# DAC_OutputStage_4.net
KiCad netlist of a schematic drawn in EAGLE
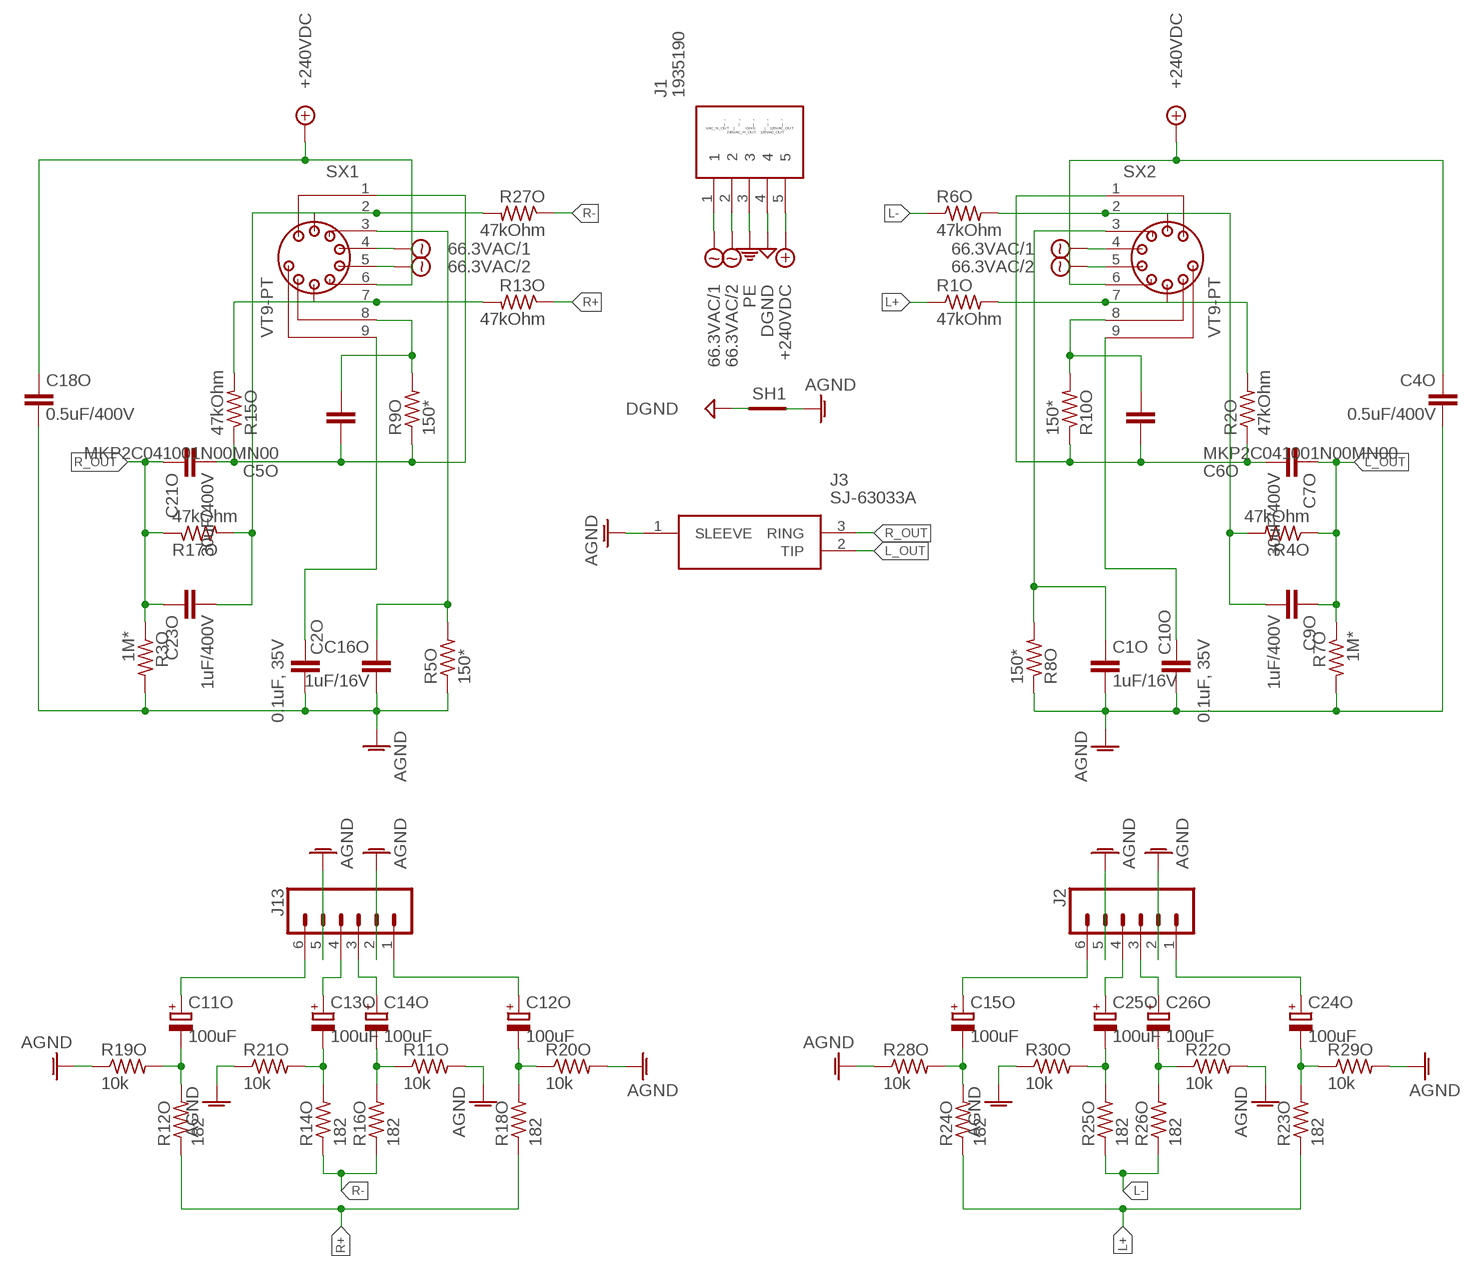
[diagram p0: schematic, sheet 1]

(export (version "E")
  (design (tool "Eeschema 10.0.6"))
  (components
    (comp (ref "C1O")
      (value "1uF/16V")
      (footprint "eagle-import:MKP2C041001N00MN00")
      (fields
        (field (name "MANUFACTURER_PART_NUMBER") "MKP2C041001N00MN00")
        (field (name "MOUSER_PART_NUMBER") "505-MKP2C0411NMN")
      )
      (libsource (lib "eagle-import") (part "MKP2C041001N00MN00"))
    )
    (comp (ref "C2O")
      (value "0.1uF, 35V")
      (footprint "eagle-import:MKS4B031002A00JC00")
      (fields
        (field (name "MANUFACTURER_PART_NUMBER") "MKS4B031002A00JC00")
        (field (name "MOUSER_PART_NUMBER") "505-MKS4B0312AJC")
      )
      (libsource (lib "eagle-import") (part "MKS4B031002A00JC00"))
    )
    (comp (ref "C4O")
      (value "0.5uF/400V")
      (footprint "eagle-import:MKP4G034705D00KSSD")
      (fields
        (field (name "MANUFACTURER_PART_NUMBER") "MKP4G034705D00KSSD")
        (field (name "MOUSER_PART_NUMBER") "505-MKP4G034705DKSSD")
      )
      (libsource (lib "eagle-import") (part "MKP4G034705D00KSSD"))
    )
    (comp (ref "C5O")
      (value "MKP2C041001N00MN00")
      (footprint "eagle-import:MKP2C041001N00MN00")
      (fields (field (name "MOUSER_PART_NUMBER") "505-MKP2C0411NMN"))
      (libsource (lib "eagle-import") (part "MKP2C041001N00MN00"))
    )
    (comp (ref "C6O")
      (value "MKP2C041001N00MN00")
      (footprint "eagle-import:MKP2C041001N00MN00")
      (fields (field (name "MOUSER_PART_NUMBER") "505-MKP2C0411NMN"))
      (libsource (lib "eagle-import") (part "MKP2C041001N00MN00"))
    )
    (comp (ref "C7O")
      (value "30uF/400V")
      (footprint "eagle-import:DCP4G053006ID2KSSD")
      (fields
        (field (name "MANUFACTURER_PART_NUMBER") "DCP4G053006ID2KSSD")
        (field (name "MOUSER_PART_NUMBER") "505-DCP4G0536ID2KSSD")
      )
      (libsource (lib "eagle-import") (part "DCP4G053006ID2KSSD"))
    )
    (comp (ref "C9O")
      (value "1uF/400V")
      (footprint "eagle-import:MKP4G041005I00JSSD")
      (fields
        (field (name "MANUFACTURER_PART_NUMBER") "MKP4G041005I00JSSD")
        (field (name "MOUSER_PART_NUMBER") "505-MKP4G041005I00JS")
      )
      (libsource (lib "eagle-import") (part "MKP4G041005I00JSSD"))
    )
    (comp (ref "C10O")
      (value "0.1uF, 35V")
      (footprint "eagle-import:MKS4B031002A00JC00")
      (fields
        (field (name "MANUFACTURER_PART_NUMBER") "MKS4B031002A00JC00")
        (field (name "MOUSER_PART_NUMBER") "505-MKS4B0312AJC")
      )
      (libsource (lib "eagle-import") (part "MKS4B031002A00JC00"))
    )
    (comp (ref "C11O")
      (value "100uF")
      (footprint "eagle-import:CAPPRD350W60D825H1300")
      (fields
        (field (name "ARROW_PART_NUMBER") "UFW1H101MPD1TD")
        (field (name "MOUSER_PART_NUMBER") "647-UFW1H101MPD1TD")
      )
      (libsource (lib "eagle-import") (part "UFW1H101MPD1TD"))
    )
    (comp (ref "C12O")
      (value "100uF")
      (footprint "eagle-import:CAPPRD350W60D825H1300")
      (fields
        (field (name "ARROW_PART_NUMBER") "UFW1H101MPD1TD")
        (field (name "MOUSER_PART_NUMBER") "647-UFW1H101MPD1TD")
      )
      (libsource (lib "eagle-import") (part "UFW1H101MPD1TD"))
    )
    (comp (ref "C13O")
      (value "100uF")
      (footprint "eagle-import:CAPPRD350W60D825H1300")
      (fields
        (field (name "ARROW_PART_NUMBER") "UFW1H101MPD1TD")
        (field (name "MOUSER_PART_NUMBER") "647-UFW1H101MPD1TD")
      )
      (libsource (lib "eagle-import") (part "UFW1H101MPD1TD"))
    )
    (comp (ref "C14O")
      (value "100uF")
      (footprint "eagle-import:CAPPRD350W60D825H1300")
      (fields
        (field (name "ARROW_PART_NUMBER") "UFW1H101MPD1TD")
        (field (name "MOUSER_PART_NUMBER") "647-UFW1H101MPD1TD")
      )
      (libsource (lib "eagle-import") (part "UFW1H101MPD1TD"))
    )
    (comp (ref "C15O")
      (value "100uF")
      (footprint "eagle-import:CAPPRD350W60D825H1300")
      (fields
        (field (name "ARROW_PART_NUMBER") "UFW1H101MPD1TD")
        (field (name "MOUSER_PART_NUMBER") "647-UFW1H101MPD1TD")
      )
      (libsource (lib "eagle-import") (part "UFW1H101MPD1TD"))
    )
    (comp (ref "C16O")
      (value "1uF/16V")
      (footprint "eagle-import:MKP2C041001N00MN00")
      (fields
        (field (name "MANUFACTURER_PART_NUMBER") "MKP2C041001N00MN00")
        (field (name "MOUSER_PART_NUMBER") "505-MKP2C0411NMN")
      )
      (libsource (lib "eagle-import") (part "MKP2C041001N00MN00"))
    )
    (comp (ref "C18O")
      (value "0.5uF/400V")
      (footprint "eagle-import:MKP4G034705D00KSSD")
      (fields
        (field (name "MANUFACTURER_PART_NUMBER") "MKP4G034705D00KSSD")
        (field (name "MOUSER_PART_NUMBER") "505-MKP4G034705DKSSD")
      )
      (libsource (lib "eagle-import") (part "MKP4G034705D00KSSD"))
    )
    (comp (ref "C21O")
      (value "30uF/400V")
      (footprint "eagle-import:DCP4G053006ID2KSSD")
      (fields
        (field (name "MANUFACTURER_PART_NUMBER") "DCP4G053006ID2KSSD")
        (field (name "MOUSER_PART_NUMBER") "505-DCP4G0536ID2KSSD")
      )
      (libsource (lib "eagle-import") (part "DCP4G053006ID2KSSD"))
    )
    (comp (ref "C23O")
      (value "1uF/400V")
      (footprint "eagle-import:MKP4G041005I00JSSD")
      (fields
        (field (name "MANUFACTURER_PART_NUMBER") "MKP4G041005I00JSSD")
        (field (name "MOUSER_PART_NUMBER") "505-MKP4G041005I00JS")
      )
      (libsource (lib "eagle-import") (part "MKP4G041005I00JSSD"))
    )
    (comp (ref "C24O")
      (value "100uF")
      (footprint "eagle-import:CAPPRD350W60D825H1300")
      (fields
        (field (name "ARROW_PART_NUMBER") "UFW1H101MPD1TD")
        (field (name "MOUSER_PART_NUMBER") "647-UFW1H101MPD1TD")
      )
      (libsource (lib "eagle-import") (part "UFW1H101MPD1TD"))
    )
    (comp (ref "C25O")
      (value "100uF")
      (footprint "eagle-import:CAPPRD350W60D825H1300")
      (fields
        (field (name "ARROW_PART_NUMBER") "UFW1H101MPD1TD")
        (field (name "MOUSER_PART_NUMBER") "647-UFW1H101MPD1TD")
      )
      (libsource (lib "eagle-import") (part "UFW1H101MPD1TD"))
    )
    (comp (ref "C26O")
      (value "100uF")
      (footprint "eagle-import:CAPPRD350W60D825H1300")
      (fields
        (field (name "ARROW_PART_NUMBER") "UFW1H101MPD1TD")
        (field (name "MOUSER_PART_NUMBER") "647-UFW1H101MPD1TD")
      )
      (libsource (lib "eagle-import") (part "UFW1H101MPD1TD"))
    )
    (comp (ref "J1")
      (value "1935190")
      (footprint "eagle-import:1935190")
      (fields (field (name "MOUSER_PART_NUMBER") "651-1935190"))
      (libsource (lib "eagle-import") (part "1935190"))
    )
    (comp (ref "J2")
      (value "CONN_06SILK_FEMALE_PTH")
      (footprint "eagle-import:1X06")
      (libsource (lib "eagle-import") (part "CONN_06SILK_FEMALE_PTH"))
    )
    (comp (ref "J3")
      (value "SJ-63033A")
      (footprint "eagle-import:SJ63033A")
      (libsource (lib "eagle-import") (part "SJ-63033A"))
    )
    (comp (ref "J13")
      (value "CONN_06SILK_FEMALE_PTH")
      (footprint "eagle-import:1X06")
      (libsource (lib "eagle-import") (part "CONN_06SILK_FEMALE_PTH"))
    )
    (comp (ref "R1O")
      (value "47kOhm")
      (footprint "eagle-import:RESAD1540W55L620D230")
      (fields
        (field (name "MANUFACTURER_PART_NUMBER") "LR1F47K")
        (field (name "MOUSER_PART_NUMBER") "279-LR1F47K")
      )
      (libsource (lib "eagle-import") (part "LR1F47K"))
    )
    (comp (ref "R2O")
      (value "47kOhm")
      (footprint "eagle-import:RESAD1540W55L620D230")
      (fields
        (field (name "MANUFACTURER_PART_NUMBER") "LR1F47K")
        (field (name "MOUSER_PART_NUMBER") "279-LR1F47K")
      )
      (libsource (lib "eagle-import") (part "LR1F47K"))
    )
    (comp (ref "R3O")
      (value "1M*")
      (footprint "eagle-import:RESAD1540W60L620D230")
      (fields
        (field (name "MANUFACTURER_PART_NUMBER") "LR1F1M0")
        (field (name "MOUSER_PART_NUMBER") "279-LR1F1M0")
      )
      (libsource (lib "eagle-import") (part "LR1F1M0"))
    )
    (comp (ref "R4O")
      (value "47kOhm")
      (footprint "eagle-import:RESAD1540W55L620D230")
      (fields
        (field (name "MANUFACTURER_PART_NUMBER") "LR1F47K")
        (field (name "MOUSER_PART_NUMBER") "279-LR1F47K")
      )
      (libsource (lib "eagle-import") (part "LR1F47K"))
    )
    (comp (ref "R5O")
      (value "150*")
      (footprint "eagle-import:RESAD1540W55L620D230")
      (fields (field (name "MANUFACTURER_PART_NUMBER") "LR1F150R"))
      (libsource (lib "eagle-import") (part "LR1F150R"))
    )
    (comp (ref "R6O")
      (value "47kOhm")
      (footprint "eagle-import:RESAD1540W55L620D230")
      (fields
        (field (name "MANUFACTURER_PART_NUMBER") "LR1F47K")
        (field (name "MOUSER_PART_NUMBER") "279-LR1F47K")
      )
      (libsource (lib "eagle-import") (part "LR1F47K"))
    )
    (comp (ref "R7O")
      (value "1M*")
      (footprint "eagle-import:RESAD1540W60L620D230")
      (fields
        (field (name "MANUFACTURER_PART_NUMBER") "LR1F1M0")
        (field (name "MOUSER_PART_NUMBER") "279-LR1F1M0")
      )
      (libsource (lib "eagle-import") (part "LR1F1M0"))
    )
    (comp (ref "R8O")
      (value "150*")
      (footprint "eagle-import:RESAD1540W55L620D230")
      (fields (field (name "MANUFACTURER_PART_NUMBER") "LR1F150R"))
      (libsource (lib "eagle-import") (part "LR1F150R"))
    )
    (comp (ref "R9O")
      (value "150*")
      (footprint "eagle-import:RESAD1540W55L620D230")
      (fields (field (name "MANUFACTURER_PART_NUMBER") "LR1F150R"))
      (libsource (lib "eagle-import") (part "LR1F150R"))
    )
    (comp (ref "R10O")
      (value "150*")
      (footprint "eagle-import:RESAD1540W55L620D230")
      (fields (field (name "MANUFACTURER_PART_NUMBER") "LR1F150R"))
      (libsource (lib "eagle-import") (part "LR1F150R"))
    )
    (comp (ref "R11O")
      (value "10k")
      (footprint "eagle-import:RESAD1540W55L620D230")
      (fields
        (field (name "MANUFACTURER_PART_NUMBER") "LR1F10K")
        (field (name "MOUSER_PART_NUMBER") "279-LR1F10K")
      )
      (libsource (lib "eagle-import") (part "LR1F10K"))
    )
    (comp (ref "R12O")
      (value "182")
      (footprint "eagle-import:RESAD1590W60L630D240")
      (fields (field (name "MANUFACTURER_PART_NUMBER") "MF0207FTE52-182R"))
      (libsource (lib "eagle-import") (part "MF0207FTE52-182R"))
    )
    (comp (ref "R13O")
      (value "47kOhm")
      (footprint "eagle-import:RESAD1540W55L620D230")
      (fields
        (field (name "MANUFACTURER_PART_NUMBER") "LR1F47K")
        (field (name "MOUSER_PART_NUMBER") "279-LR1F47K")
      )
      (libsource (lib "eagle-import") (part "LR1F47K"))
    )
    (comp (ref "R14O")
      (value "182")
      (footprint "eagle-import:RESAD1590W60L630D240")
      (fields (field (name "MANUFACTURER_PART_NUMBER") "MF0207FTE52-182R"))
      (libsource (lib "eagle-import") (part "MF0207FTE52-182R"))
    )
    (comp (ref "R15O")
      (value "47kOhm")
      (footprint "eagle-import:RESAD1540W55L620D230")
      (fields
        (field (name "MANUFACTURER_PART_NUMBER") "LR1F47K")
        (field (name "MOUSER_PART_NUMBER") "279-LR1F47K")
      )
      (libsource (lib "eagle-import") (part "LR1F47K"))
    )
    (comp (ref "R16O")
      (value "182")
      (footprint "eagle-import:RESAD1590W60L630D240")
      (fields (field (name "MANUFACTURER_PART_NUMBER") "MF0207FTE52-182R"))
      (libsource (lib "eagle-import") (part "MF0207FTE52-182R"))
    )
    (comp (ref "R17O")
      (value "47kOhm")
      (footprint "eagle-import:RESAD1540W55L620D230")
      (fields
        (field (name "MANUFACTURER_PART_NUMBER") "LR1F47K")
        (field (name "MOUSER_PART_NUMBER") "279-LR1F47K")
      )
      (libsource (lib "eagle-import") (part "LR1F47K"))
    )
    (comp (ref "R18O")
      (value "182")
      (footprint "eagle-import:RESAD1590W60L630D240")
      (fields (field (name "MANUFACTURER_PART_NUMBER") "MF0207FTE52-182R"))
      (libsource (lib "eagle-import") (part "MF0207FTE52-182R"))
    )
    (comp (ref "R19O")
      (value "10k")
      (footprint "eagle-import:RESAD1540W55L620D230")
      (fields
        (field (name "MANUFACTURER_PART_NUMBER") "LR1F10K")
        (field (name "MOUSER_PART_NUMBER") "279-LR1F10K")
      )
      (libsource (lib "eagle-import") (part "LR1F10K"))
    )
    (comp (ref "R20O")
      (value "10k")
      (footprint "eagle-import:RESAD1540W55L620D230")
      (fields
        (field (name "MANUFACTURER_PART_NUMBER") "LR1F10K")
        (field (name "MOUSER_PART_NUMBER") "279-LR1F10K")
      )
      (libsource (lib "eagle-import") (part "LR1F10K"))
    )
    (comp (ref "R21O")
      (value "10k")
      (footprint "eagle-import:RESAD1540W55L620D230")
      (fields
        (field (name "MANUFACTURER_PART_NUMBER") "LR1F10K")
        (field (name "MOUSER_PART_NUMBER") "279-LR1F10K")
      )
      (libsource (lib "eagle-import") (part "LR1F10K"))
    )
    (comp (ref "R22O")
      (value "10k")
      (footprint "eagle-import:RESAD1540W55L620D230")
      (fields
        (field (name "MANUFACTURER_PART_NUMBER") "LR1F10K")
        (field (name "MOUSER_PART_NUMBER") "279-LR1F10K")
      )
      (libsource (lib "eagle-import") (part "LR1F10K"))
    )
    (comp (ref "R23O")
      (value "182")
      (footprint "eagle-import:RESAD1590W60L630D240")
      (fields (field (name "MANUFACTURER_PART_NUMBER") "MF0207FTE52-182R"))
      (libsource (lib "eagle-import") (part "MF0207FTE52-182R"))
    )
    (comp (ref "R24O")
      (value "182")
      (footprint "eagle-import:RESAD1590W60L630D240")
      (fields (field (name "MANUFACTURER_PART_NUMBER") "MF0207FTE52-182R"))
      (libsource (lib "eagle-import") (part "MF0207FTE52-182R"))
    )
    (comp (ref "R25O")
      (value "182")
      (footprint "eagle-import:RESAD1590W60L630D240")
      (fields (field (name "MANUFACTURER_PART_NUMBER") "MF0207FTE52-182R"))
      (libsource (lib "eagle-import") (part "MF0207FTE52-182R"))
    )
    (comp (ref "R26O")
      (value "182")
      (footprint "eagle-import:RESAD1590W60L630D240")
      (fields (field (name "MANUFACTURER_PART_NUMBER") "MF0207FTE52-182R"))
      (libsource (lib "eagle-import") (part "MF0207FTE52-182R"))
    )
    (comp (ref "R27O")
      (value "47kOhm")
      (footprint "eagle-import:RESAD1540W55L620D230")
      (fields
        (field (name "MANUFACTURER_PART_NUMBER") "LR1F47K")
        (field (name "MOUSER_PART_NUMBER") "279-LR1F47K")
      )
      (libsource (lib "eagle-import") (part "LR1F47K"))
    )
    (comp (ref "R28O")
      (value "10k")
      (footprint "eagle-import:RESAD1540W55L620D230")
      (fields
        (field (name "MANUFACTURER_PART_NUMBER") "LR1F10K")
        (field (name "MOUSER_PART_NUMBER") "279-LR1F10K")
      )
      (libsource (lib "eagle-import") (part "LR1F10K"))
    )
    (comp (ref "R29O")
      (value "10k")
      (footprint "eagle-import:RESAD1540W55L620D230")
      (fields
        (field (name "MANUFACTURER_PART_NUMBER") "LR1F10K")
        (field (name "MOUSER_PART_NUMBER") "279-LR1F10K")
      )
      (libsource (lib "eagle-import") (part "LR1F10K"))
    )
    (comp (ref "R30O")
      (value "10k")
      (footprint "eagle-import:RESAD1540W55L620D230")
      (fields
        (field (name "MANUFACTURER_PART_NUMBER") "LR1F10K")
        (field (name "MOUSER_PART_NUMBER") "279-LR1F10K")
      )
      (libsource (lib "eagle-import") (part "LR1F10K"))
    )
    (comp (ref "SH1")
      (value "SHORTA5")
      (footprint "eagle-import:SHORT_ALL-50")
      (libsource (lib "eagle-import") (part "SHORTA5"))
    )
    (comp (ref "SX1")
      (value "VT9-PT")
      (footprint "eagle-import:VT9-PT")
      (libsource (lib "eagle-import") (part "VT9-PT"))
    )
    (comp (ref "SX2")
      (value "VT9-PT")
      (footprint "eagle-import:VT9-PT")
      (libsource (lib "eagle-import") (part "VT9-PT"))
    )
  )
  (nets
    (net (code "1") (name "+240VDC") (class "Default")
      (node (ref "C18O") (pin "1") (pinfunction "1_1") (pintype "passive"))
      (node (ref "C4O") (pin "1") (pinfunction "1_1") (pintype "passive"))
      (node (ref "J1") (pin "5") (pinfunction "5_5") (pintype "bidirectional"))
      (node (ref "SX1") (pin "6") (pinfunction "6_6") (pintype "passive"))
      (node (ref "SX2") (pin "6") (pinfunction "6_6") (pintype "passive"))
    )
    (net (code "2") (name "66.3VAC{slash}1") (class "Default")
      (node (ref "J1") (pin "1") (pinfunction "1_1") (pintype "bidirectional"))
      (node (ref "SX1") (pin "4") (pinfunction "4_4") (pintype "passive"))
      (node (ref "SX2") (pin "4") (pinfunction "4_4") (pintype "passive"))
    )
    (net (code "3") (name "66.3VAC{slash}2") (class "Default")
      (node (ref "J1") (pin "2") (pinfunction "2_2") (pintype "bidirectional"))
      (node (ref "SX1") (pin "5") (pinfunction "5_5") (pintype "passive"))
      (node (ref "SX2") (pin "5") (pinfunction "5_5") (pintype "passive"))
    )
    (net (code "4") (name "AGND") (class "Default")
      (node (ref "C10O") (pin "2") (pinfunction "2_2") (pintype "passive"))
      (node (ref "C16O") (pin "2") (pinfunction "2_2") (pintype "passive"))
      (node (ref "C18O") (pin "2") (pinfunction "2_2") (pintype "passive"))
      (node (ref "C1O") (pin "2") (pinfunction "2_2") (pintype "passive"))
      (node (ref "C2O") (pin "2") (pinfunction "2_2") (pintype "passive"))
      (node (ref "C4O") (pin "2") (pinfunction "2_2") (pintype "passive"))
      (node (ref "J13") (pin "2") (pinfunction "2_2") (pintype "passive"))
      (node (ref "J13") (pin "5") (pinfunction "5_5") (pintype "passive"))
      (node (ref "J2") (pin "2") (pinfunction "2_2") (pintype "passive"))
      (node (ref "J2") (pin "5") (pinfunction "5_5") (pintype "passive"))
      (node (ref "J3") (pin "1") (pinfunction "SLEEVE_1") (pintype "bidirectional"))
      (node (ref "R11O") (pin "2") (pinfunction "2_2") (pintype "passive"))
      (node (ref "R19O") (pin "1") (pinfunction "1_1") (pintype "passive"))
      (node (ref "R20O") (pin "2") (pinfunction "2_2") (pintype "passive"))
      (node (ref "R21O") (pin "1") (pinfunction "1_1") (pintype "passive"))
      (node (ref "R22O") (pin "2") (pinfunction "2_2") (pintype "passive"))
      (node (ref "R28O") (pin "1") (pinfunction "1_1") (pintype "passive"))
      (node (ref "R29O") (pin "2") (pinfunction "2_2") (pintype "passive"))
      (node (ref "R30O") (pin "1") (pinfunction "1_1") (pintype "passive"))
      (node (ref "R3O") (pin "2") (pinfunction "2_2") (pintype "passive"))
      (node (ref "R5O") (pin "1") (pinfunction "1_1") (pintype "passive"))
      (node (ref "R7O") (pin "2") (pinfunction "2_2") (pintype "passive"))
      (node (ref "R8O") (pin "1") (pinfunction "1_1") (pintype "passive"))
      (node (ref "SH1") (pin "2") (pinfunction "P$2_2") (pintype "bidirectional"))
    )
    (net (code "5") (name "DGND") (class "Default")
      (node (ref "J1") (pin "4") (pinfunction "4_4") (pintype "bidirectional"))
      (node (ref "SH1") (pin "1") (pinfunction "P$1_1") (pintype "bidirectional"))
    )
    (net (code "6") (name "L+") (class "Default")
      (node (ref "R1O") (pin "1") (pinfunction "1_1") (pintype "passive"))
      (node (ref "R23O") (pin "1") (pinfunction "1_1") (pintype "passive"))
      (node (ref "R24O") (pin "1") (pinfunction "1_1") (pintype "passive"))
    )
    (net (code "7") (name "L-") (class "Default")
      (node (ref "R25O") (pin "1") (pinfunction "1_1") (pintype "passive"))
      (node (ref "R26O") (pin "1") (pinfunction "1_1") (pintype "passive"))
      (node (ref "R6O") (pin "1") (pinfunction "1_1") (pintype "passive"))
    )
    (net (code "8") (name "L_OUT") (class "Default")
      (node (ref "C7O") (pin "1") (pinfunction "1_1") (pintype "passive"))
      (node (ref "C9O") (pin "1") (pinfunction "1_1") (pintype "passive"))
      (node (ref "J3") (pin "2") (pinfunction "TIP_2") (pintype "bidirectional"))
      (node (ref "R4O") (pin "1") (pinfunction "1_1") (pintype "passive"))
      (node (ref "R7O") (pin "1") (pinfunction "1_1") (pintype "passive"))
    )
    (net (code "9") (name "Net-(C1O-Pad1)") (class "Default")
      (node (ref "C1O") (pin "1") (pinfunction "1_1") (pintype "passive"))
      (node (ref "R8O") (pin "2") (pinfunction "2_2") (pintype "passive"))
      (node (ref "SX2") (pin "3") (pinfunction "3_3") (pintype "passive"))
    )
    (net (code "10") (name "Net-(C2O-Pad1)") (class "Default")
      (node (ref "C2O") (pin "1") (pinfunction "1_1") (pintype "passive"))
      (node (ref "SX1") (pin "9") (pinfunction "9_9") (pintype "passive"))
    )
    (net (code "11") (name "Net-(C5O-Pad2)") (class "Default")
      (node (ref "C5O") (pin "2") (pinfunction "2_2") (pintype "passive"))
      (node (ref "R9O") (pin "2") (pinfunction "2_2") (pintype "passive"))
      (node (ref "SX1") (pin "8") (pinfunction "8_8") (pintype "passive"))
    )
    (net (code "12") (name "Net-(C6O-Pad1)") (class "Default")
      (node (ref "C6O") (pin "1") (pinfunction "1_1") (pintype "passive"))
      (node (ref "C7O") (pin "2") (pinfunction "2_2") (pintype "passive"))
      (node (ref "R10O") (pin "1") (pinfunction "1_1") (pintype "passive"))
      (node (ref "R2O") (pin "1") (pinfunction "1_1") (pintype "passive"))
      (node (ref "SX2") (pin "1") (pinfunction "1_1") (pintype "passive"))
    )
    (net (code "13") (name "Net-(C6O-Pad2)") (class "Default")
      (node (ref "C6O") (pin "2") (pinfunction "2_2") (pintype "passive"))
      (node (ref "R10O") (pin "2") (pinfunction "2_2") (pintype "passive"))
      (node (ref "SX2") (pin "8") (pinfunction "8_8") (pintype "passive"))
    )
    (net (code "14") (name "Net-(C9O-Pad2)") (class "Default")
      (node (ref "C9O") (pin "2") (pinfunction "2_2") (pintype "passive"))
      (node (ref "R4O") (pin "2") (pinfunction "2_2") (pintype "passive"))
      (node (ref "R6O") (pin "2") (pinfunction "2_2") (pintype "passive"))
      (node (ref "SX2") (pin "2") (pinfunction "2_2") (pintype "passive"))
    )
    (net (code "15") (name "Net-(C10O-Pad1)") (class "Default")
      (node (ref "C10O") (pin "1") (pinfunction "1_1") (pintype "passive"))
      (node (ref "SX2") (pin "9") (pinfunction "9_9") (pintype "passive"))
    )
    (net (code "16") (name "Net-(C11O-+)") (class "Default")
      (node (ref "C11O") (pin "1") (pinfunction "+_1") (pintype "passive"))
      (node (ref "J13") (pin "6") (pinfunction "6_6") (pintype "passive"))
    )
    (net (code "17") (name "Net-(C11O--)") (class "Default")
      (node (ref "C11O") (pin "2") (pinfunction "-_2") (pintype "passive"))
      (node (ref "R12O") (pin "2") (pinfunction "2_2") (pintype "passive"))
      (node (ref "R19O") (pin "2") (pinfunction "2_2") (pintype "passive"))
    )
    (net (code "18") (name "Net-(C12O-+)") (class "Default")
      (node (ref "C12O") (pin "1") (pinfunction "+_1") (pintype "passive"))
      (node (ref "J13") (pin "1") (pinfunction "1_1") (pintype "passive"))
    )
    (net (code "19") (name "Net-(C12O--)") (class "Default")
      (node (ref "C12O") (pin "2") (pinfunction "-_2") (pintype "passive"))
      (node (ref "R18O") (pin "2") (pinfunction "2_2") (pintype "passive"))
      (node (ref "R20O") (pin "1") (pinfunction "1_1") (pintype "passive"))
    )
    (net (code "20") (name "Net-(C13O-+)") (class "Default")
      (node (ref "C13O") (pin "1") (pinfunction "+_1") (pintype "passive"))
      (node (ref "J13") (pin "4") (pinfunction "4_4") (pintype "passive"))
    )
    (net (code "21") (name "Net-(C13O--)") (class "Default")
      (node (ref "C13O") (pin "2") (pinfunction "-_2") (pintype "passive"))
      (node (ref "R14O") (pin "2") (pinfunction "2_2") (pintype "passive"))
      (node (ref "R21O") (pin "2") (pinfunction "2_2") (pintype "passive"))
    )
    (net (code "22") (name "Net-(C14O-+)") (class "Default")
      (node (ref "C14O") (pin "1") (pinfunction "+_1") (pintype "passive"))
      (node (ref "J13") (pin "3") (pinfunction "3_3") (pintype "passive"))
    )
    (net (code "23") (name "Net-(C14O--)") (class "Default")
      (node (ref "C14O") (pin "2") (pinfunction "-_2") (pintype "passive"))
      (node (ref "R11O") (pin "1") (pinfunction "1_1") (pintype "passive"))
      (node (ref "R16O") (pin "2") (pinfunction "2_2") (pintype "passive"))
    )
    (net (code "24") (name "Net-(C15O-+)") (class "Default")
      (node (ref "C15O") (pin "1") (pinfunction "+_1") (pintype "passive"))
      (node (ref "J2") (pin "6") (pinfunction "6_6") (pintype "passive"))
    )
    (net (code "25") (name "Net-(C15O--)") (class "Default")
      (node (ref "C15O") (pin "2") (pinfunction "-_2") (pintype "passive"))
      (node (ref "R24O") (pin "2") (pinfunction "2_2") (pintype "passive"))
      (node (ref "R28O") (pin "2") (pinfunction "2_2") (pintype "passive"))
    )
    (net (code "26") (name "Net-(C16O-Pad1)") (class "Default")
      (node (ref "C16O") (pin "1") (pinfunction "1_1") (pintype "passive"))
      (node (ref "R5O") (pin "2") (pinfunction "2_2") (pintype "passive"))
      (node (ref "SX1") (pin "3") (pinfunction "3_3") (pintype "passive"))
    )
    (net (code "27") (name "Net-(C21O-Pad2)") (class "Default")
      (node (ref "C21O") (pin "2") (pinfunction "2_2") (pintype "passive"))
      (node (ref "C5O") (pin "1") (pinfunction "1_1") (pintype "passive"))
      (node (ref "R15O") (pin "1") (pinfunction "1_1") (pintype "passive"))
      (node (ref "R9O") (pin "1") (pinfunction "1_1") (pintype "passive"))
      (node (ref "SX1") (pin "1") (pinfunction "1_1") (pintype "passive"))
    )
    (net (code "28") (name "Net-(C23O-Pad2)") (class "Default")
      (node (ref "C23O") (pin "2") (pinfunction "2_2") (pintype "passive"))
      (node (ref "R17O") (pin "2") (pinfunction "2_2") (pintype "passive"))
      (node (ref "R27O") (pin "2") (pinfunction "2_2") (pintype "passive"))
      (node (ref "SX1") (pin "2") (pinfunction "2_2") (pintype "passive"))
    )
    (net (code "29") (name "Net-(C24O-+)") (class "Default")
      (node (ref "C24O") (pin "1") (pinfunction "+_1") (pintype "passive"))
      (node (ref "J2") (pin "1") (pinfunction "1_1") (pintype "passive"))
    )
    (net (code "30") (name "Net-(C24O--)") (class "Default")
      (node (ref "C24O") (pin "2") (pinfunction "-_2") (pintype "passive"))
      (node (ref "R23O") (pin "2") (pinfunction "2_2") (pintype "passive"))
      (node (ref "R29O") (pin "1") (pinfunction "1_1") (pintype "passive"))
    )
    (net (code "31") (name "Net-(C25O-+)") (class "Default")
      (node (ref "C25O") (pin "1") (pinfunction "+_1") (pintype "passive"))
      (node (ref "J2") (pin "4") (pinfunction "4_4") (pintype "passive"))
    )
    (net (code "32") (name "Net-(C25O--)") (class "Default")
      (node (ref "C25O") (pin "2") (pinfunction "-_2") (pintype "passive"))
      (node (ref "R25O") (pin "2") (pinfunction "2_2") (pintype "passive"))
      (node (ref "R30O") (pin "2") (pinfunction "2_2") (pintype "passive"))
    )
    (net (code "33") (name "Net-(C26O-+)") (class "Default")
      (node (ref "C26O") (pin "1") (pinfunction "+_1") (pintype "passive"))
      (node (ref "J2") (pin "3") (pinfunction "3_3") (pintype "passive"))
    )
    (net (code "34") (name "Net-(C26O--)") (class "Default")
      (node (ref "C26O") (pin "2") (pinfunction "-_2") (pintype "passive"))
      (node (ref "R22O") (pin "1") (pinfunction "1_1") (pintype "passive"))
      (node (ref "R26O") (pin "2") (pinfunction "2_2") (pintype "passive"))
    )
    (net (code "35") (name "Net-(R1O-Pad2)") (class "Default")
      (node (ref "R1O") (pin "2") (pinfunction "2_2") (pintype "passive"))
      (node (ref "R2O") (pin "2") (pinfunction "2_2") (pintype "passive"))
      (node (ref "SX2") (pin "7") (pinfunction "7_7") (pintype "passive"))
    )
    (net (code "36") (name "Net-(R13O-Pad2)") (class "Default")
      (node (ref "R13O") (pin "2") (pinfunction "2_2") (pintype "passive"))
      (node (ref "R15O") (pin "2") (pinfunction "2_2") (pintype "passive"))
      (node (ref "SX1") (pin "7") (pinfunction "7_7") (pintype "passive"))
    )
    (net (code "37") (name "PE") (class "Default")
      (node (ref "J1") (pin "3") (pinfunction "3_3") (pintype "bidirectional"))
    )
    (net (code "38") (name "R+") (class "Default")
      (node (ref "R12O") (pin "1") (pinfunction "1_1") (pintype "passive"))
      (node (ref "R13O") (pin "1") (pinfunction "1_1") (pintype "passive"))
      (node (ref "R18O") (pin "1") (pinfunction "1_1") (pintype "passive"))
    )
    (net (code "39") (name "R-") (class "Default")
      (node (ref "R14O") (pin "1") (pinfunction "1_1") (pintype "passive"))
      (node (ref "R16O") (pin "1") (pinfunction "1_1") (pintype "passive"))
      (node (ref "R27O") (pin "1") (pinfunction "1_1") (pintype "passive"))
    )
    (net (code "40") (name "R_OUT") (class "Default")
      (node (ref "C21O") (pin "1") (pinfunction "1_1") (pintype "passive"))
      (node (ref "C23O") (pin "1") (pinfunction "1_1") (pintype "passive"))
      (node (ref "J3") (pin "3") (pinfunction "RING_3") (pintype "bidirectional"))
      (node (ref "R17O") (pin "1") (pinfunction "1_1") (pintype "passive"))
      (node (ref "R3O") (pin "1") (pinfunction "1_1") (pintype "passive"))
    )
  )
)
